# 05-Backplane_Connector.net
KiCad netlist of a schematic drawn in Altium Designer
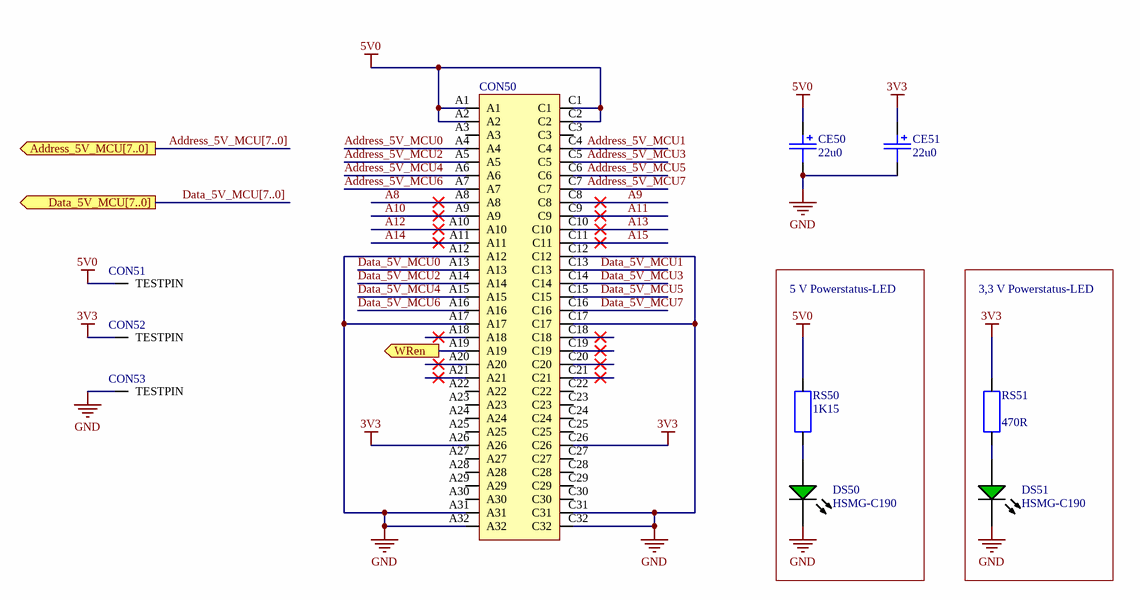
[diagram p0: 05-Backplane_Connector.SchDoc]

(export (version "E")
  (design (tool "Eeschema 10.0.6"))
  (components
    (comp (ref "CE50")
      (value "22u0")
      (footprint "PcbLib_EES:CE_002_THT_2MM20_S_A")
      (description "Teapo Elko TA Series 22µF 50V")
      (libsource (lib "Schlib_EES") (part "CE_RADIAL_22U_50V0_20PO_R07"))
    )
    (comp (ref "CE51")
      (value "22u0")
      (footprint "PcbLib_EES:CE_002_THT_2MM20_S_A")
      (description "Teapo Elko TA Series 22µF 50V")
      (libsource (lib "Schlib_EES") (part "CE_RADIAL_22U_50V0_20PO_R07"))
    )
    (comp (ref "CON50")
      (value "103-40034")
      (footprint "PcbLib_EES:CON_064_THT_2MM54_M")
      (description "C- Male Connector According to IEC 60603-2 (DIN 41612)")
      (fields (field (name "EDITOR_DATE") "li_08.12.2020"))
      (libsource (lib "Schlib_EES") (part "CON_064_M_2MM54_L_X"))
    )
    (comp (ref "CON51")
      (value "CON_001_M_MM000_S_X_MILL-MAX_TP")
      (footprint "CON_001_THT_MM000_S_D")
      (description "MILL-MAX_TP")
      (fields (field (name "MANUFACTURER") "MILL-MAX") (field (name "EDITOR_DATE") "boos, 06.02.2014"))
      (libsource (lib "Bauteildb") (part "CON_001_M_MM000_S_X_MILL-MAX_TP"))
    )
    (comp (ref "CON52")
      (value "CON_001_M_MM000_S_X_MILL-MAX_TP")
      (footprint "CON_001_THT_MM000_S_D")
      (description "MILL-MAX_TP")
      (fields (field (name "MANUFACTURER") "MILL-MAX") (field (name "EDITOR_DATE") "boos, 06.02.2014"))
      (libsource (lib "Bauteildb") (part "CON_001_M_MM000_S_X_MILL-MAX_TP"))
    )
    (comp (ref "CON53")
      (value "CON_001_M_MM000_S_X_MILL-MAX_TP")
      (footprint "CON_001_THT_MM000_S_D")
      (description "MILL-MAX_TP")
      (fields (field (name "MANUFACTURER") "MILL-MAX") (field (name "EDITOR_DATE") "boos, 06.02.2014"))
      (libsource (lib "Bauteildb") (part "CON_001_M_MM000_S_X_MILL-MAX_TP"))
    )
    (comp (ref "DS50")
      (value "HSMG-C190")
      (footprint "AVAG-HSMX-C190_V")
      (description "Chip LED, Green, 2.2 V, -40 to 85 degC, 2-Pin SMD, RoHS, Tape and Reel")
      (libsource (lib "Altium Content Vault") (part "LED-GREEN-AK-2"))
    )
    (comp (ref "DS51")
      (value "HSMG-C190")
      (footprint "AVAG-HSMX-C190_V")
      (description "Chip LED, Green, 2.2 V, -40 to 85 degC, 2-Pin SMD, RoHS, Tape and Reel")
      (libsource (lib "Altium Content Vault") (part "LED-GREEN-AK-2"))
    )
    (comp (ref "RS50")
      (value "RS")
      (footprint "0603_A")
      (fields
        (field (name "RESISTANCE") "1K15")
        (field (name "POWER") "W100")
        (field (name "TOLERANCE") "1P00")
        (field (name "MANUFACTURER") "Yageo")
      )
      (libsource (lib "Bauteildb") (part "RS"))
    )
    (comp (ref "RS51")
      (value "RS")
      (footprint "0603_A")
      (fields
        (field (name "RESISTANCE") "470R")
        (field (name "POWER") "W100")
        (field (name "TOLERANCE") "1P00")
        (field (name "MANUFACTURER") "Yageo")
      )
      (libsource (lib "Bauteildb") (part "RS"))
    )
  )
  (nets
    (net (code "1") (name "/A8") (class "Default")
      (node (ref "CON50") (pin "A8") (pinfunction "A8_A8") (pintype "passive"))
    )
    (net (code "2") (name "/A9") (class "Default")
      (node (ref "CON50") (pin "C8") (pinfunction "C8_C8") (pintype "passive"))
    )
    (net (code "3") (name "/A10") (class "Default")
      (node (ref "CON50") (pin "A9") (pinfunction "A9_A9") (pintype "passive"))
    )
    (net (code "4") (name "/A11") (class "Default")
      (node (ref "CON50") (pin "C9") (pinfunction "C9_C9") (pintype "passive"))
    )
    (net (code "5") (name "/A12") (class "Default")
      (node (ref "CON50") (pin "A10") (pinfunction "A10_A10") (pintype "passive"))
    )
    (net (code "6") (name "/A13") (class "Default")
      (node (ref "CON50") (pin "C10") (pinfunction "C10_C10") (pintype "passive"))
    )
    (net (code "7") (name "/A14") (class "Default")
      (node (ref "CON50") (pin "A11") (pinfunction "A11_A11") (pintype "passive"))
    )
    (net (code "8") (name "/A15") (class "Default")
      (node (ref "CON50") (pin "C11") (pinfunction "C11_C11") (pintype "passive"))
    )
    (net (code "9") (name "/Address_5V_MCU0") (class "Default")
      (node (ref "CON50") (pin "A4") (pinfunction "A4_A4") (pintype "passive"))
    )
    (net (code "10") (name "/Address_5V_MCU1") (class "Default")
      (node (ref "CON50") (pin "C4") (pinfunction "C4_C4") (pintype "passive"))
    )
    (net (code "11") (name "/Address_5V_MCU2") (class "Default")
      (node (ref "CON50") (pin "A5") (pinfunction "A5_A5") (pintype "passive"))
    )
    (net (code "12") (name "/Address_5V_MCU3") (class "Default")
      (node (ref "CON50") (pin "C5") (pinfunction "C5_C5") (pintype "passive"))
    )
    (net (code "13") (name "/Address_5V_MCU4") (class "Default")
      (node (ref "CON50") (pin "A6") (pinfunction "A6_A6") (pintype "passive"))
    )
    (net (code "14") (name "/Address_5V_MCU5") (class "Default")
      (node (ref "CON50") (pin "C6") (pinfunction "C6_C6") (pintype "passive"))
    )
    (net (code "15") (name "/Address_5V_MCU6") (class "Default")
      (node (ref "CON50") (pin "A7") (pinfunction "A7_A7") (pintype "passive"))
    )
    (net (code "16") (name "/Address_5V_MCU7") (class "Default")
      (node (ref "CON50") (pin "C7") (pinfunction "C7_C7") (pintype "passive"))
    )
    (net (code "18") (name "/Data_5V_MCU0") (class "Default")
      (node (ref "CON50") (pin "A13") (pinfunction "A13_A13") (pintype "passive"))
    )
    (net (code "19") (name "/Data_5V_MCU1") (class "Default")
      (node (ref "CON50") (pin "C13") (pinfunction "C13_C13") (pintype "passive"))
    )
    (net (code "20") (name "/Data_5V_MCU2") (class "Default")
      (node (ref "CON50") (pin "A14") (pinfunction "A14_A14") (pintype "passive"))
    )
    (net (code "21") (name "/Data_5V_MCU3") (class "Default")
      (node (ref "CON50") (pin "C14") (pinfunction "C14_C14") (pintype "passive"))
    )
    (net (code "22") (name "/Data_5V_MCU4") (class "Default")
      (node (ref "CON50") (pin "A15") (pinfunction "A15_A15") (pintype "passive"))
    )
    (net (code "23") (name "/Data_5V_MCU5") (class "Default")
      (node (ref "CON50") (pin "C15") (pinfunction "C15_C15") (pintype "passive"))
    )
    (net (code "24") (name "/Data_5V_MCU6") (class "Default")
      (node (ref "CON50") (pin "A16") (pinfunction "A16_A16") (pintype "passive"))
    )
    (net (code "25") (name "/Data_5V_MCU7") (class "Default")
      (node (ref "CON50") (pin "C16") (pinfunction "C16_C16") (pintype "passive"))
    )
    (net (code "27") (name "/WRen") (class "Default")
      (node (ref "CON50") (pin "A19") (pinfunction "A19_A19") (pintype "passive"))
    )
    (net (code "28") (name "3V3") (class "Default")
      (node (ref "CE51") (pin "1") (pinfunction "1_1") (pintype "passive"))
      (node (ref "CON50") (pin "A26") (pinfunction "A26_A26") (pintype "passive"))
      (node (ref "CON50") (pin "C26") (pinfunction "C26_C26") (pintype "passive"))
      (node (ref "CON52") (pin "1") (pinfunction "TESTPIN_1") (pintype "passive"))
      (node (ref "RS51") (pin "2") (pintype "passive"))
    )
    (net (code "29") (name "5V0") (class "Default")
      (node (ref "CE50") (pin "1") (pinfunction "1_1") (pintype "passive"))
      (node (ref "CON50") (pin "A1") (pinfunction "A1_A1") (pintype "passive"))
      (node (ref "CON50") (pin "A2") (pinfunction "A2_A2") (pintype "passive"))
      (node (ref "CON50") (pin "C1") (pinfunction "C1_C1") (pintype "passive"))
      (node (ref "CON50") (pin "C2") (pinfunction "C2_C2") (pintype "passive"))
      (node (ref "CON51") (pin "1") (pinfunction "TESTPIN_1") (pintype "passive"))
      (node (ref "RS50") (pin "2") (pintype "passive"))
    )
    (net (code "30") (name "GND") (class "Default")
      (node (ref "CE50") (pin "2") (pinfunction "2_2") (pintype "passive"))
      (node (ref "CE51") (pin "2") (pinfunction "2_2") (pintype "passive"))
      (node (ref "CON50") (pin "A12") (pinfunction "A12_A12") (pintype "passive"))
      (node (ref "CON50") (pin "A17") (pinfunction "A17_A17") (pintype "passive"))
      (node (ref "CON50") (pin "A31") (pinfunction "A31_A31") (pintype "passive"))
      (node (ref "CON50") (pin "A32") (pinfunction "A32_A32") (pintype "passive"))
      (node (ref "CON50") (pin "C12") (pinfunction "C12_C12") (pintype "passive"))
      (node (ref "CON50") (pin "C17") (pinfunction "C17_C17") (pintype "passive"))
      (node (ref "CON50") (pin "C31") (pinfunction "C31_C31") (pintype "passive"))
      (node (ref "CON50") (pin "C32") (pinfunction "C32_C32") (pintype "passive"))
      (node (ref "CON53") (pin "1") (pinfunction "TESTPIN_1") (pintype "passive"))
      (node (ref "DS50") (pin "2") (pinfunction "K_2") (pintype "passive"))
      (node (ref "DS51") (pin "2") (pinfunction "K_2") (pintype "passive"))
    )
    (net (code "31") (name "Net-(DS50-A)") (class "Default")
      (node (ref "DS50") (pin "1") (pinfunction "A_1") (pintype "passive"))
      (node (ref "RS50") (pin "1") (pintype "passive"))
    )
    (net (code "32") (name "Net-(DS51-A)") (class "Default")
      (node (ref "DS51") (pin "1") (pinfunction "A_1") (pintype "passive"))
      (node (ref "RS51") (pin "1") (pintype "passive"))
    )
    (net (code "33") (name "unconnected-(CON50-PadA3)") (class "Default")
      (node (ref "CON50") (pin "A3") (pinfunction "A3_A3") (pintype "passive"))
    )
    (net (code "34") (name "unconnected-(CON50-PadA18)") (class "Default")
      (node (ref "CON50") (pin "A18") (pinfunction "A18_A18") (pintype "passive"))
    )
    (net (code "35") (name "unconnected-(CON50-PadA20)") (class "Default")
      (node (ref "CON50") (pin "A20") (pinfunction "A20_A20") (pintype "passive"))
    )
    (net (code "36") (name "unconnected-(CON50-PadA21)") (class "Default")
      (node (ref "CON50") (pin "A21") (pinfunction "A21_A21") (pintype "passive"))
    )
    (net (code "37") (name "unconnected-(CON50-PadA22)") (class "Default")
      (node (ref "CON50") (pin "A22") (pinfunction "A22_A22") (pintype "passive"))
    )
    (net (code "38") (name "unconnected-(CON50-PadA23)") (class "Default")
      (node (ref "CON50") (pin "A23") (pinfunction "A23_A23") (pintype "passive"))
    )
    (net (code "39") (name "unconnected-(CON50-PadA24)") (class "Default")
      (node (ref "CON50") (pin "A24") (pinfunction "A24_A24") (pintype "passive"))
    )
    (net (code "40") (name "unconnected-(CON50-PadA25)") (class "Default")
      (node (ref "CON50") (pin "A25") (pinfunction "A25_A25") (pintype "passive"))
    )
    (net (code "41") (name "unconnected-(CON50-PadA27)") (class "Default")
      (node (ref "CON50") (pin "A27") (pinfunction "A27_A27") (pintype "passive"))
    )
    (net (code "42") (name "unconnected-(CON50-PadA28)") (class "Default")
      (node (ref "CON50") (pin "A28") (pinfunction "A28_A28") (pintype "passive"))
    )
    (net (code "43") (name "unconnected-(CON50-PadA29)") (class "Default")
      (node (ref "CON50") (pin "A29") (pinfunction "A29_A29") (pintype "passive"))
    )
    (net (code "44") (name "unconnected-(CON50-PadA30)") (class "Default")
      (node (ref "CON50") (pin "A30") (pinfunction "A30_A30") (pintype "passive"))
    )
    (net (code "45") (name "unconnected-(CON50-PadC3)") (class "Default")
      (node (ref "CON50") (pin "C3") (pinfunction "C3_C3") (pintype "passive"))
    )
    (net (code "46") (name "unconnected-(CON50-PadC18)") (class "Default")
      (node (ref "CON50") (pin "C18") (pinfunction "C18_C18") (pintype "passive"))
    )
    (net (code "47") (name "unconnected-(CON50-PadC19)") (class "Default")
      (node (ref "CON50") (pin "C19") (pinfunction "C19_C19") (pintype "passive"))
    )
    (net (code "48") (name "unconnected-(CON50-PadC20)") (class "Default")
      (node (ref "CON50") (pin "C20") (pinfunction "C20_C20") (pintype "passive"))
    )
    (net (code "49") (name "unconnected-(CON50-PadC21)") (class "Default")
      (node (ref "CON50") (pin "C21") (pinfunction "C21_C21") (pintype "passive"))
    )
    (net (code "50") (name "unconnected-(CON50-PadC22)") (class "Default")
      (node (ref "CON50") (pin "C22") (pinfunction "C22_C22") (pintype "passive"))
    )
    (net (code "51") (name "unconnected-(CON50-PadC23)") (class "Default")
      (node (ref "CON50") (pin "C23") (pinfunction "C23_C23") (pintype "passive"))
    )
    (net (code "52") (name "unconnected-(CON50-PadC24)") (class "Default")
      (node (ref "CON50") (pin "C24") (pinfunction "C24_C24") (pintype "passive"))
    )
    (net (code "53") (name "unconnected-(CON50-PadC25)") (class "Default")
      (node (ref "CON50") (pin "C25") (pinfunction "C25_C25") (pintype "passive"))
    )
    (net (code "54") (name "unconnected-(CON50-PadC27)") (class "Default")
      (node (ref "CON50") (pin "C27") (pinfunction "C27_C27") (pintype "passive"))
    )
    (net (code "55") (name "unconnected-(CON50-PadC28)") (class "Default")
      (node (ref "CON50") (pin "C28") (pinfunction "C28_C28") (pintype "passive"))
    )
    (net (code "56") (name "unconnected-(CON50-PadC29)") (class "Default")
      (node (ref "CON50") (pin "C29") (pinfunction "C29_C29") (pintype "passive"))
    )
    (net (code "57") (name "unconnected-(CON50-PadC30)") (class "Default")
      (node (ref "CON50") (pin "C30") (pinfunction "C30_C30") (pintype "passive"))
    )
  )
)
